# Sensores.net
KiCad netlist of a schematic drawn in Altium Designer
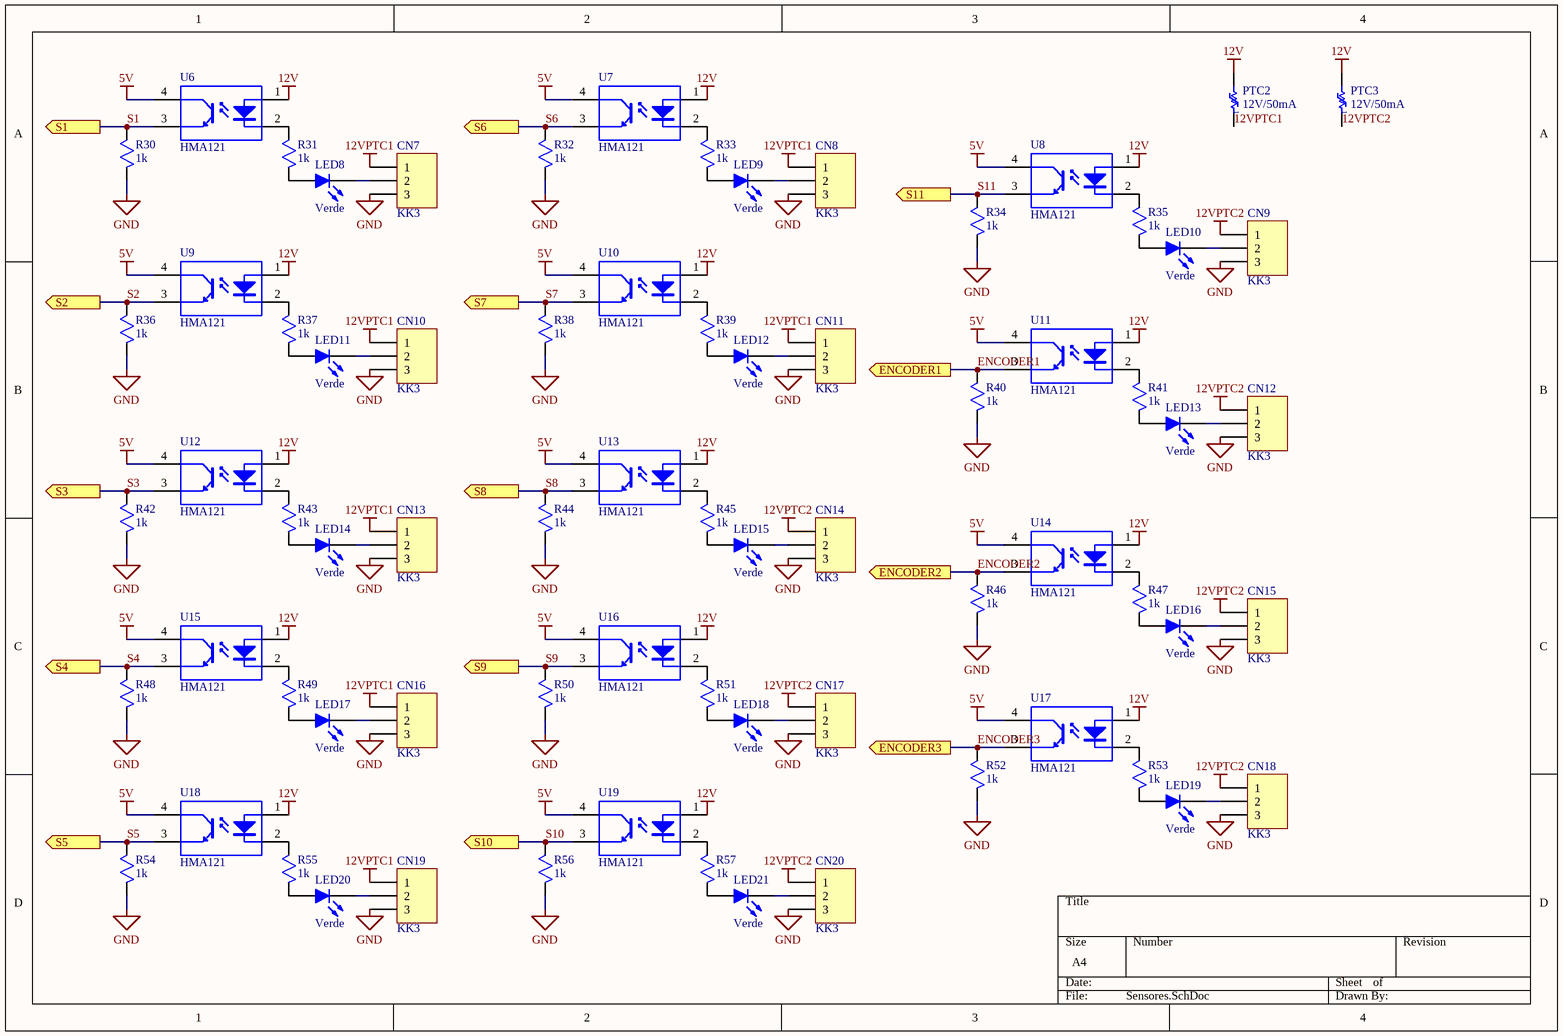
[diagram p0: Sensores.SchDoc]

(export (version "E")
  (design (tool "Eeschema 10.0.6"))
  (components
    (comp (ref "CN7")
      (value "KK3")
      (footprint "KK3 - 2.54mm")
      (description "Conector Linear tipo KK de 3 vias")
      (libsource (lib "conectores") (part "KK3"))
    )
    (comp (ref "CN8")
      (value "KK3")
      (footprint "KK3 - 2.54mm")
      (description "Conector Linear tipo KK de 3 vias")
      (libsource (lib "conectores") (part "KK3"))
    )
    (comp (ref "CN9")
      (value "KK3")
      (footprint "KK3 - 2.54mm")
      (description "Conector Linear tipo KK de 3 vias")
      (libsource (lib "conectores") (part "KK3"))
    )
    (comp (ref "CN10")
      (value "KK3")
      (footprint "KK3 - 2.54mm")
      (description "Conector Linear tipo KK de 3 vias")
      (libsource (lib "conectores") (part "KK3"))
    )
    (comp (ref "CN11")
      (value "KK3")
      (footprint "KK3 - 2.54mm")
      (description "Conector Linear tipo KK de 3 vias")
      (libsource (lib "conectores") (part "KK3"))
    )
    (comp (ref "CN12")
      (value "KK3")
      (footprint "KK3 - 2.54mm")
      (description "Conector Linear tipo KK de 3 vias")
      (libsource (lib "conectores") (part "KK3"))
    )
    (comp (ref "CN13")
      (value "KK3")
      (footprint "KK3 - 2.54mm")
      (description "Conector Linear tipo KK de 3 vias")
      (libsource (lib "conectores") (part "KK3"))
    )
    (comp (ref "CN14")
      (value "KK3")
      (footprint "KK3 - 2.54mm")
      (description "Conector Linear tipo KK de 3 vias")
      (libsource (lib "conectores") (part "KK3"))
    )
    (comp (ref "CN15")
      (value "KK3")
      (footprint "KK3 - 2.54mm")
      (description "Conector Linear tipo KK de 3 vias")
      (libsource (lib "conectores") (part "KK3"))
    )
    (comp (ref "CN16")
      (value "KK3")
      (footprint "KK3 - 2.54mm")
      (description "Conector Linear tipo KK de 3 vias")
      (libsource (lib "conectores") (part "KK3"))
    )
    (comp (ref "CN17")
      (value "KK3")
      (footprint "KK3 - 2.54mm")
      (description "Conector Linear tipo KK de 3 vias")
      (libsource (lib "conectores") (part "KK3"))
    )
    (comp (ref "CN18")
      (value "KK3")
      (footprint "KK3 - 2.54mm")
      (description "Conector Linear tipo KK de 3 vias")
      (libsource (lib "conectores") (part "KK3"))
    )
    (comp (ref "CN19")
      (value "KK3")
      (footprint "KK3 - 2.54mm")
      (description "Conector Linear tipo KK de 3 vias")
      (libsource (lib "conectores") (part "KK3"))
    )
    (comp (ref "CN20")
      (value "KK3")
      (footprint "KK3 - 2.54mm")
      (description "Conector Linear tipo KK de 3 vias")
      (libsource (lib "conectores") (part "KK3"))
    )
    (comp (ref "LED8")
      (value "Verde")
      (footprint "LED_SMD_0805")
      (description "Led")
      (fields (field (name "MANUFACTURER") "Generic Components") (field (name "PUBLISHER") "Altium Limited"))
      (libsource (lib "diodos_transistores") (part "Led"))
    )
    (comp (ref "LED9")
      (value "Verde")
      (footprint "LED_SMD_0805")
      (description "Led")
      (fields (field (name "MANUFACTURER") "Generic Components") (field (name "PUBLISHER") "Altium Limited"))
      (libsource (lib "diodos_transistores") (part "Led"))
    )
    (comp (ref "LED10")
      (value "Verde")
      (footprint "LED_SMD_0805")
      (description "Led")
      (fields (field (name "MANUFACTURER") "Generic Components") (field (name "PUBLISHER") "Altium Limited"))
      (libsource (lib "diodos_transistores") (part "Led"))
    )
    (comp (ref "LED11")
      (value "Verde")
      (footprint "LED_SMD_0805")
      (description "Led")
      (fields (field (name "MANUFACTURER") "Generic Components") (field (name "PUBLISHER") "Altium Limited"))
      (libsource (lib "diodos_transistores") (part "Led"))
    )
    (comp (ref "LED12")
      (value "Verde")
      (footprint "LED_SMD_0805")
      (description "Led")
      (fields (field (name "MANUFACTURER") "Generic Components") (field (name "PUBLISHER") "Altium Limited"))
      (libsource (lib "diodos_transistores") (part "Led"))
    )
    (comp (ref "LED13")
      (value "Verde")
      (footprint "LED_SMD_0805")
      (description "Led")
      (fields (field (name "MANUFACTURER") "Generic Components") (field (name "PUBLISHER") "Altium Limited"))
      (libsource (lib "diodos_transistores") (part "Led"))
    )
    (comp (ref "LED14")
      (value "Verde")
      (footprint "LED_SMD_0805")
      (description "Led")
      (fields (field (name "MANUFACTURER") "Generic Components") (field (name "PUBLISHER") "Altium Limited"))
      (libsource (lib "diodos_transistores") (part "Led"))
    )
    (comp (ref "LED15")
      (value "Verde")
      (footprint "LED_SMD_0805")
      (description "Led")
      (fields (field (name "MANUFACTURER") "Generic Components") (field (name "PUBLISHER") "Altium Limited"))
      (libsource (lib "diodos_transistores") (part "Led"))
    )
    (comp (ref "LED16")
      (value "Verde")
      (footprint "LED_SMD_0805")
      (description "Led")
      (fields (field (name "MANUFACTURER") "Generic Components") (field (name "PUBLISHER") "Altium Limited"))
      (libsource (lib "diodos_transistores") (part "Led"))
    )
    (comp (ref "LED17")
      (value "Verde")
      (footprint "LED_SMD_0805")
      (description "Led")
      (fields (field (name "MANUFACTURER") "Generic Components") (field (name "PUBLISHER") "Altium Limited"))
      (libsource (lib "diodos_transistores") (part "Led"))
    )
    (comp (ref "LED18")
      (value "Verde")
      (footprint "LED_SMD_0805")
      (description "Led")
      (fields (field (name "MANUFACTURER") "Generic Components") (field (name "PUBLISHER") "Altium Limited"))
      (libsource (lib "diodos_transistores") (part "Led"))
    )
    (comp (ref "LED19")
      (value "Verde")
      (footprint "LED_SMD_0805")
      (description "Led")
      (fields (field (name "MANUFACTURER") "Generic Components") (field (name "PUBLISHER") "Altium Limited"))
      (libsource (lib "diodos_transistores") (part "Led"))
    )
    (comp (ref "LED20")
      (value "Verde")
      (footprint "LED_SMD_0805")
      (description "Led")
      (fields (field (name "MANUFACTURER") "Generic Components") (field (name "PUBLISHER") "Altium Limited"))
      (libsource (lib "diodos_transistores") (part "Led"))
    )
    (comp (ref "LED21")
      (value "Verde")
      (footprint "LED_SMD_0805")
      (description "Led")
      (fields (field (name "MANUFACTURER") "Generic Components") (field (name "PUBLISHER") "Altium Limited"))
      (libsource (lib "diodos_transistores") (part "Led"))
    )
    (comp (ref "PTC2")
      (value "12V/50mA")
      (footprint "PTC-200")
      (description "Termistor")
      (libsource (lib "comps_passivos") (part "PTC"))
    )
    (comp (ref "PTC3")
      (value "12V/50mA")
      (footprint "PTC-200")
      (description "Termistor")
      (libsource (lib "comps_passivos") (part "PTC"))
    )
    (comp (ref "R30")
      (value "1k")
      (footprint "SMD0805")
      (description "Resistor")
      (libsource (lib "passivos") (part "Resistor"))
    )
    (comp (ref "R31")
      (value "1k")
      (footprint "SMD0805")
      (description "Resistor")
      (libsource (lib "passivos") (part "Resistor"))
    )
    (comp (ref "R32")
      (value "1k")
      (footprint "SMD0805")
      (description "Resistor")
      (libsource (lib "passivos") (part "Resistor"))
    )
    (comp (ref "R33")
      (value "1k")
      (footprint "SMD0805")
      (description "Resistor")
      (libsource (lib "passivos") (part "Resistor"))
    )
    (comp (ref "R34")
      (value "1k")
      (footprint "SMD0805")
      (description "Resistor")
      (libsource (lib "passivos") (part "Resistor"))
    )
    (comp (ref "R35")
      (value "1k")
      (footprint "SMD0805")
      (description "Resistor")
      (libsource (lib "passivos") (part "Resistor"))
    )
    (comp (ref "R36")
      (value "1k")
      (footprint "SMD0805")
      (description "Resistor")
      (libsource (lib "passivos") (part "Resistor"))
    )
    (comp (ref "R37")
      (value "1k")
      (footprint "SMD0805")
      (description "Resistor")
      (libsource (lib "passivos") (part "Resistor"))
    )
    (comp (ref "R38")
      (value "1k")
      (footprint "SMD0805")
      (description "Resistor")
      (libsource (lib "passivos") (part "Resistor"))
    )
    (comp (ref "R39")
      (value "1k")
      (footprint "SMD0805")
      (description "Resistor")
      (libsource (lib "passivos") (part "Resistor"))
    )
    (comp (ref "R40")
      (value "1k")
      (footprint "SMD0805")
      (description "Resistor")
      (libsource (lib "passivos") (part "Resistor"))
    )
    (comp (ref "R41")
      (value "1k")
      (footprint "SMD0805")
      (description "Resistor")
      (libsource (lib "passivos") (part "Resistor"))
    )
    (comp (ref "R42")
      (value "1k")
      (footprint "SMD0805")
      (description "Resistor")
      (libsource (lib "passivos") (part "Resistor"))
    )
    (comp (ref "R43")
      (value "1k")
      (footprint "SMD0805")
      (description "Resistor")
      (libsource (lib "passivos") (part "Resistor"))
    )
    (comp (ref "R44")
      (value "1k")
      (footprint "SMD0805")
      (description "Resistor")
      (libsource (lib "passivos") (part "Resistor"))
    )
    (comp (ref "R45")
      (value "1k")
      (footprint "SMD0805")
      (description "Resistor")
      (libsource (lib "passivos") (part "Resistor"))
    )
    (comp (ref "R46")
      (value "1k")
      (footprint "SMD0805")
      (description "Resistor")
      (libsource (lib "passivos") (part "Resistor"))
    )
    (comp (ref "R47")
      (value "1k")
      (footprint "SMD0805")
      (description "Resistor")
      (libsource (lib "passivos") (part "Resistor"))
    )
    (comp (ref "R48")
      (value "1k")
      (footprint "SMD0805")
      (description "Resistor")
      (libsource (lib "passivos") (part "Resistor"))
    )
    (comp (ref "R49")
      (value "1k")
      (footprint "SMD0805")
      (description "Resistor")
      (libsource (lib "passivos") (part "Resistor"))
    )
    (comp (ref "R50")
      (value "1k")
      (footprint "SMD0805")
      (description "Resistor")
      (libsource (lib "passivos") (part "Resistor"))
    )
    (comp (ref "R51")
      (value "1k")
      (footprint "SMD0805")
      (description "Resistor")
      (libsource (lib "passivos") (part "Resistor"))
    )
    (comp (ref "R52")
      (value "1k")
      (footprint "SMD0805")
      (description "Resistor")
      (libsource (lib "passivos") (part "Resistor"))
    )
    (comp (ref "R53")
      (value "1k")
      (footprint "SMD0805")
      (description "Resistor")
      (libsource (lib "passivos") (part "Resistor"))
    )
    (comp (ref "R54")
      (value "1k")
      (footprint "SMD0805")
      (description "Resistor")
      (libsource (lib "passivos") (part "Resistor"))
    )
    (comp (ref "R55")
      (value "1k")
      (footprint "SMD0805")
      (description "Resistor")
      (libsource (lib "passivos") (part "Resistor"))
    )
    (comp (ref "R56")
      (value "1k")
      (footprint "SMD0805")
      (description "Resistor")
      (libsource (lib "passivos") (part "Resistor"))
    )
    (comp (ref "R57")
      (value "1k")
      (footprint "SMD0805")
      (description "Resistor")
      (libsource (lib "passivos") (part "Resistor"))
    )
    (comp (ref "U6")
      (value "HMA121")
      (footprint "SO4")
      (description "Phototransistor Optocoupler SMD full Pptch mini-flat type")
      (fields (field (name "MANUFACTURER") "Generic Components") (field (name "PUBLISHER") "Altium Limited"))
      (libsource (lib "diodos_transistores") (part "HMA"))
    )
    (comp (ref "U7")
      (value "HMA121")
      (footprint "SO4")
      (description "Phototransistor Optocoupler SMD full Pptch mini-flat type")
      (fields (field (name "MANUFACTURER") "Generic Components") (field (name "PUBLISHER") "Altium Limited"))
      (libsource (lib "diodos_transistores") (part "HMA"))
    )
    (comp (ref "U8")
      (value "HMA121")
      (footprint "SO4")
      (description "Phototransistor Optocoupler SMD full Pptch mini-flat type")
      (fields (field (name "MANUFACTURER") "Generic Components") (field (name "PUBLISHER") "Altium Limited"))
      (libsource (lib "diodos_transistores") (part "HMA"))
    )
    (comp (ref "U9")
      (value "HMA121")
      (footprint "SO4")
      (description "Phototransistor Optocoupler SMD full Pptch mini-flat type")
      (fields (field (name "MANUFACTURER") "Generic Components") (field (name "PUBLISHER") "Altium Limited"))
      (libsource (lib "diodos_transistores") (part "HMA"))
    )
    (comp (ref "U10")
      (value "HMA121")
      (footprint "SO4")
      (description "Phototransistor Optocoupler SMD full Pptch mini-flat type")
      (fields (field (name "MANUFACTURER") "Generic Components") (field (name "PUBLISHER") "Altium Limited"))
      (libsource (lib "diodos_transistores") (part "HMA"))
    )
    (comp (ref "U11")
      (value "HMA121")
      (footprint "SO4")
      (description "Phototransistor Optocoupler SMD full Pptch mini-flat type")
      (fields (field (name "MANUFACTURER") "Generic Components") (field (name "PUBLISHER") "Altium Limited"))
      (libsource (lib "diodos_transistores") (part "HMA"))
    )
    (comp (ref "U12")
      (value "HMA121")
      (footprint "SO4")
      (description "Phototransistor Optocoupler SMD full Pptch mini-flat type")
      (fields (field (name "MANUFACTURER") "Generic Components") (field (name "PUBLISHER") "Altium Limited"))
      (libsource (lib "diodos_transistores") (part "HMA"))
    )
    (comp (ref "U13")
      (value "HMA121")
      (footprint "SO4")
      (description "Phototransistor Optocoupler SMD full Pptch mini-flat type")
      (fields (field (name "MANUFACTURER") "Generic Components") (field (name "PUBLISHER") "Altium Limited"))
      (libsource (lib "diodos_transistores") (part "HMA"))
    )
    (comp (ref "U14")
      (value "HMA121")
      (footprint "SO4")
      (description "Phototransistor Optocoupler SMD full Pptch mini-flat type")
      (fields (field (name "MANUFACTURER") "Generic Components") (field (name "PUBLISHER") "Altium Limited"))
      (libsource (lib "diodos_transistores") (part "HMA"))
    )
    (comp (ref "U15")
      (value "HMA121")
      (footprint "SO4")
      (description "Phototransistor Optocoupler SMD full Pptch mini-flat type")
      (fields (field (name "MANUFACTURER") "Generic Components") (field (name "PUBLISHER") "Altium Limited"))
      (libsource (lib "diodos_transistores") (part "HMA"))
    )
    (comp (ref "U16")
      (value "HMA121")
      (footprint "SO4")
      (description "Phototransistor Optocoupler SMD full Pptch mini-flat type")
      (fields (field (name "MANUFACTURER") "Generic Components") (field (name "PUBLISHER") "Altium Limited"))
      (libsource (lib "diodos_transistores") (part "HMA"))
    )
    (comp (ref "U17")
      (value "HMA121")
      (footprint "SO4")
      (description "Phototransistor Optocoupler SMD full Pptch mini-flat type")
      (fields (field (name "MANUFACTURER") "Generic Components") (field (name "PUBLISHER") "Altium Limited"))
      (libsource (lib "diodos_transistores") (part "HMA"))
    )
    (comp (ref "U18")
      (value "HMA121")
      (footprint "SO4")
      (description "Phototransistor Optocoupler SMD full Pptch mini-flat type")
      (fields (field (name "MANUFACTURER") "Generic Components") (field (name "PUBLISHER") "Altium Limited"))
      (libsource (lib "diodos_transistores") (part "HMA"))
    )
    (comp (ref "U19")
      (value "HMA121")
      (footprint "SO4")
      (description "Phototransistor Optocoupler SMD full Pptch mini-flat type")
      (fields (field (name "MANUFACTURER") "Generic Components") (field (name "PUBLISHER") "Altium Limited"))
      (libsource (lib "diodos_transistores") (part "HMA"))
    )
  )
  (nets
    (net (code "1") (name "/ENCODER1") (class "Default")
      (node (ref "R40") (pin "1") (pinfunction "1_1") (pintype "passive"))
      (node (ref "U11") (pin "3") (pinfunction "E_3") (pintype "passive"))
    )
    (net (code "2") (name "/ENCODER2") (class "Default")
      (node (ref "R46") (pin "1") (pinfunction "1_1") (pintype "passive"))
      (node (ref "U14") (pin "3") (pinfunction "E_3") (pintype "passive"))
    )
    (net (code "3") (name "/ENCODER3") (class "Default")
      (node (ref "R52") (pin "1") (pinfunction "1_1") (pintype "passive"))
      (node (ref "U17") (pin "3") (pinfunction "E_3") (pintype "passive"))
    )
    (net (code "4") (name "/S1") (class "Default")
      (node (ref "R30") (pin "1") (pinfunction "1_1") (pintype "passive"))
      (node (ref "U6") (pin "3") (pinfunction "E_3") (pintype "passive"))
    )
    (net (code "5") (name "/S2") (class "Default")
      (node (ref "R36") (pin "1") (pinfunction "1_1") (pintype "passive"))
      (node (ref "U9") (pin "3") (pinfunction "E_3") (pintype "passive"))
    )
    (net (code "6") (name "/S3") (class "Default")
      (node (ref "R42") (pin "1") (pinfunction "1_1") (pintype "passive"))
      (node (ref "U12") (pin "3") (pinfunction "E_3") (pintype "passive"))
    )
    (net (code "7") (name "/S4") (class "Default")
      (node (ref "R48") (pin "1") (pinfunction "1_1") (pintype "passive"))
      (node (ref "U15") (pin "3") (pinfunction "E_3") (pintype "passive"))
    )
    (net (code "8") (name "/S5") (class "Default")
      (node (ref "R54") (pin "1") (pinfunction "1_1") (pintype "passive"))
      (node (ref "U18") (pin "3") (pinfunction "E_3") (pintype "passive"))
    )
    (net (code "9") (name "/S6") (class "Default")
      (node (ref "R32") (pin "1") (pinfunction "1_1") (pintype "passive"))
      (node (ref "U7") (pin "3") (pinfunction "E_3") (pintype "passive"))
    )
    (net (code "10") (name "/S7") (class "Default")
      (node (ref "R38") (pin "1") (pinfunction "1_1") (pintype "passive"))
      (node (ref "U10") (pin "3") (pinfunction "E_3") (pintype "passive"))
    )
    (net (code "11") (name "/S8") (class "Default")
      (node (ref "R44") (pin "1") (pinfunction "1_1") (pintype "passive"))
      (node (ref "U13") (pin "3") (pinfunction "E_3") (pintype "passive"))
    )
    (net (code "12") (name "/S9") (class "Default")
      (node (ref "R50") (pin "1") (pinfunction "1_1") (pintype "passive"))
      (node (ref "U16") (pin "3") (pinfunction "E_3") (pintype "passive"))
    )
    (net (code "13") (name "/S10") (class "Default")
      (node (ref "R56") (pin "1") (pinfunction "1_1") (pintype "passive"))
      (node (ref "U19") (pin "3") (pinfunction "E_3") (pintype "passive"))
    )
    (net (code "14") (name "/S11") (class "Default")
      (node (ref "R34") (pin "1") (pinfunction "1_1") (pintype "passive"))
      (node (ref "U8") (pin "3") (pinfunction "E_3") (pintype "passive"))
    )
    (net (code "15") (name "5V") (class "Default")
      (node (ref "U10") (pin "4") (pinfunction "C_4") (pintype "passive"))
      (node (ref "U11") (pin "4") (pinfunction "C_4") (pintype "passive"))
      (node (ref "U12") (pin "4") (pinfunction "C_4") (pintype "passive"))
      (node (ref "U13") (pin "4") (pinfunction "C_4") (pintype "passive"))
      (node (ref "U14") (pin "4") (pinfunction "C_4") (pintype "passive"))
      (node (ref "U15") (pin "4") (pinfunction "C_4") (pintype "passive"))
      (node (ref "U16") (pin "4") (pinfunction "C_4") (pintype "passive"))
      (node (ref "U17") (pin "4") (pinfunction "C_4") (pintype "passive"))
      (node (ref "U18") (pin "4") (pinfunction "C_4") (pintype "passive"))
      (node (ref "U19") (pin "4") (pinfunction "C_4") (pintype "passive"))
      (node (ref "U6") (pin "4") (pinfunction "C_4") (pintype "passive"))
      (node (ref "U7") (pin "4") (pinfunction "C_4") (pintype "passive"))
      (node (ref "U8") (pin "4") (pinfunction "C_4") (pintype "passive"))
      (node (ref "U9") (pin "4") (pinfunction "C_4") (pintype "passive"))
    )
    (net (code "16") (name "12V") (class "Default")
      (node (ref "PTC2") (pin "2") (pinfunction "2_2") (pintype "passive"))
      (node (ref "PTC3") (pin "2") (pinfunction "2_2") (pintype "passive"))
      (node (ref "U10") (pin "1") (pinfunction "A_1") (pintype "passive"))
      (node (ref "U11") (pin "1") (pinfunction "A_1") (pintype "passive"))
      (node (ref "U12") (pin "1") (pinfunction "A_1") (pintype "passive"))
      (node (ref "U13") (pin "1") (pinfunction "A_1") (pintype "passive"))
      (node (ref "U14") (pin "1") (pinfunction "A_1") (pintype "passive"))
      (node (ref "U15") (pin "1") (pinfunction "A_1") (pintype "passive"))
      (node (ref "U16") (pin "1") (pinfunction "A_1") (pintype "passive"))
      (node (ref "U17") (pin "1") (pinfunction "A_1") (pintype "passive"))
      (node (ref "U18") (pin "1") (pinfunction "A_1") (pintype "passive"))
      (node (ref "U19") (pin "1") (pinfunction "A_1") (pintype "passive"))
      (node (ref "U6") (pin "1") (pinfunction "A_1") (pintype "passive"))
      (node (ref "U7") (pin "1") (pinfunction "A_1") (pintype "passive"))
      (node (ref "U8") (pin "1") (pinfunction "A_1") (pintype "passive"))
      (node (ref "U9") (pin "1") (pinfunction "A_1") (pintype "passive"))
    )
    (net (code "17") (name "12VPTC1") (class "Default")
      (node (ref "CN10") (pin "1") (pinfunction "1_1") (pintype "passive"))
      (node (ref "CN11") (pin "1") (pinfunction "1_1") (pintype "passive"))
      (node (ref "CN13") (pin "1") (pinfunction "1_1") (pintype "passive"))
      (node (ref "CN16") (pin "1") (pinfunction "1_1") (pintype "passive"))
      (node (ref "CN19") (pin "1") (pinfunction "1_1") (pintype "passive"))
      (node (ref "CN7") (pin "1") (pinfunction "1_1") (pintype "passive"))
      (node (ref "CN8") (pin "1") (pinfunction "1_1") (pintype "passive"))
      (node (ref "PTC2") (pin "1") (pinfunction "1_1") (pintype "passive"))
    )
    (net (code "18") (name "12VPTC2") (class "Default")
      (node (ref "CN12") (pin "1") (pinfunction "1_1") (pintype "passive"))
      (node (ref "CN14") (pin "1") (pinfunction "1_1") (pintype "passive"))
      (node (ref "CN15") (pin "1") (pinfunction "1_1") (pintype "passive"))
      (node (ref "CN17") (pin "1") (pinfunction "1_1") (pintype "passive"))
      (node (ref "CN18") (pin "1") (pinfunction "1_1") (pintype "passive"))
      (node (ref "CN20") (pin "1") (pinfunction "1_1") (pintype "passive"))
      (node (ref "CN9") (pin "1") (pinfunction "1_1") (pintype "passive"))
      (node (ref "PTC3") (pin "1") (pinfunction "1_1") (pintype "passive"))
    )
    (net (code "19") (name "GND") (class "Default")
      (node (ref "CN10") (pin "3") (pinfunction "3_3") (pintype "passive"))
      (node (ref "CN11") (pin "3") (pinfunction "3_3") (pintype "passive"))
      (node (ref "CN12") (pin "3") (pinfunction "3_3") (pintype "passive"))
      (node (ref "CN13") (pin "3") (pinfunction "3_3") (pintype "passive"))
      (node (ref "CN14") (pin "3") (pinfunction "3_3") (pintype "passive"))
      (node (ref "CN15") (pin "3") (pinfunction "3_3") (pintype "passive"))
      (node (ref "CN16") (pin "3") (pinfunction "3_3") (pintype "passive"))
      (node (ref "CN17") (pin "3") (pinfunction "3_3") (pintype "passive"))
      (node (ref "CN18") (pin "3") (pinfunction "3_3") (pintype "passive"))
      (node (ref "CN19") (pin "3") (pinfunction "3_3") (pintype "passive"))
      (node (ref "CN20") (pin "3") (pinfunction "3_3") (pintype "passive"))
      (node (ref "CN7") (pin "3") (pinfunction "3_3") (pintype "passive"))
      (node (ref "CN8") (pin "3") (pinfunction "3_3") (pintype "passive"))
      (node (ref "CN9") (pin "3") (pinfunction "3_3") (pintype "passive"))
      (node (ref "R30") (pin "2") (pinfunction "2_2") (pintype "passive"))
      (node (ref "R32") (pin "2") (pinfunction "2_2") (pintype "passive"))
      (node (ref "R34") (pin "2") (pinfunction "2_2") (pintype "passive"))
      (node (ref "R36") (pin "2") (pinfunction "2_2") (pintype "passive"))
      (node (ref "R38") (pin "2") (pinfunction "2_2") (pintype "passive"))
      (node (ref "R40") (pin "2") (pinfunction "2_2") (pintype "passive"))
      (node (ref "R42") (pin "2") (pinfunction "2_2") (pintype "passive"))
      (node (ref "R44") (pin "2") (pinfunction "2_2") (pintype "passive"))
      (node (ref "R46") (pin "2") (pinfunction "2_2") (pintype "passive"))
      (node (ref "R48") (pin "2") (pinfunction "2_2") (pintype "passive"))
      (node (ref "R50") (pin "2") (pinfunction "2_2") (pintype "passive"))
      (node (ref "R52") (pin "2") (pinfunction "2_2") (pintype "passive"))
      (node (ref "R54") (pin "2") (pinfunction "2_2") (pintype "passive"))
      (node (ref "R56") (pin "2") (pinfunction "2_2") (pintype "passive"))
    )
    (net (code "20") (name "Net-(LED8-A)") (class "Default")
      (node (ref "LED8") (pin "1") (pinfunction "A_1") (pintype "passive"))
      (node (ref "R31") (pin "1") (pinfunction "1_1") (pintype "passive"))
    )
    (net (code "21") (name "Net-(LED8-K)") (class "Default")
      (node (ref "CN7") (pin "2") (pinfunction "2_2") (pintype "passive"))
      (node (ref "LED8") (pin "2") (pinfunction "K_2") (pintype "passive"))
    )
    (net (code "22") (name "Net-(LED9-A)") (class "Default")
      (node (ref "LED9") (pin "1") (pinfunction "A_1") (pintype "passive"))
      (node (ref "R33") (pin "1") (pinfunction "1_1") (pintype "passive"))
    )
    (net (code "23") (name "Net-(LED9-K)") (class "Default")
      (node (ref "CN8") (pin "2") (pinfunction "2_2") (pintype "passive"))
      (node (ref "LED9") (pin "2") (pinfunction "K_2") (pintype "passive"))
    )
    (net (code "24") (name "Net-(LED10-A)") (class "Default")
      (node (ref "LED10") (pin "1") (pinfunction "A_1") (pintype "passive"))
      (node (ref "R35") (pin "1") (pinfunction "1_1") (pintype "passive"))
    )
    (net (code "25") (name "Net-(LED10-K)") (class "Default")
      (node (ref "CN9") (pin "2") (pinfunction "2_2") (pintype "passive"))
      (node (ref "LED10") (pin "2") (pinfunction "K_2") (pintype "passive"))
    )
    (net (code "26") (name "Net-(LED11-A)") (class "Default")
      (node (ref "LED11") (pin "1") (pinfunction "A_1") (pintype "passive"))
      (node (ref "R37") (pin "1") (pinfunction "1_1") (pintype "passive"))
    )
    (net (code "27") (name "Net-(LED11-K)") (class "Default")
      (node (ref "CN10") (pin "2") (pinfunction "2_2") (pintype "passive"))
      (node (ref "LED11") (pin "2") (pinfunction "K_2") (pintype "passive"))
    )
    (net (code "28") (name "Net-(LED12-A)") (class "Default")
      (node (ref "LED12") (pin "1") (pinfunction "A_1") (pintype "passive"))
      (node (ref "R39") (pin "1") (pinfunction "1_1") (pintype "passive"))
    )
    (net (code "29") (name "Net-(LED12-K)") (class "Default")
      (node (ref "CN11") (pin "2") (pinfunction "2_2") (pintype "passive"))
      (node (ref "LED12") (pin "2") (pinfunction "K_2") (pintype "passive"))
    )
    (net (code "30") (name "Net-(LED13-A)") (class "Default")
      (node (ref "LED13") (pin "1") (pinfunction "A_1") (pintype "passive"))
      (node (ref "R41") (pin "1") (pinfunction "1_1") (pintype "passive"))
    )
    (net (code "31") (name "Net-(LED13-K)") (class "Default")
      (node (ref "CN12") (pin "2") (pinfunction "2_2") (pintype "passive"))
      (node (ref "LED13") (pin "2") (pinfunction "K_2") (pintype "passive"))
    )
    (net (code "32") (name "Net-(LED14-A)") (class "Default")
      (node (ref "LED14") (pin "1") (pinfunction "A_1") (pintype "passive"))
      (node (ref "R43") (pin "1") (pinfunction "1_1") (pintype "passive"))
    )
    (net (code "33") (name "Net-(LED14-K)") (class "Default")
      (node (ref "CN13") (pin "2") (pinfunction "2_2") (pintype "passive"))
      (node (ref "LED14") (pin "2") (pinfunction "K_2") (pintype "passive"))
    )
    (net (code "34") (name "Net-(LED15-A)") (class "Default")
      (node (ref "LED15") (pin "1") (pinfunction "A_1") (pintype "passive"))
      (node (ref "R45") (pin "1") (pinfunction "1_1") (pintype "passive"))
    )
    (net (code "35") (name "Net-(LED15-K)") (class "Default")
      (node (ref "CN14") (pin "2") (pinfunction "2_2") (pintype "passive"))
      (node (ref "LED15") (pin "2") (pinfunction "K_2") (pintype "passive"))
    )
    (net (code "36") (name "Net-(LED16-A)") (class "Default")
      (node (ref "LED16") (pin "1") (pinfunction "A_1") (pintype "passive"))
      (node (ref "R47") (pin "1") (pinfunction "1_1") (pintype "passive"))
    )
    (net (code "37") (name "Net-(LED16-K)") (class "Default")
      (node (ref "CN15") (pin "2") (pinfunction "2_2") (pintype "passive"))
      (node (ref "LED16") (pin "2") (pinfunction "K_2") (pintype "passive"))
    )
    (net (code "38") (name "Net-(LED17-A)") (class "Default")
      (node (ref "LED17") (pin "1") (pinfunction "A_1") (pintype "passive"))
      (node (ref "R49") (pin "1") (pinfunction "1_1") (pintype "passive"))
    )
    (net (code "39") (name "Net-(LED17-K)") (class "Default")
      (node (ref "CN16") (pin "2") (pinfunction "2_2") (pintype "passive"))
      (node (ref "LED17") (pin "2") (pinfunction "K_2") (pintype "passive"))
    )
    (net (code "40") (name "Net-(LED18-A)") (class "Default")
      (node (ref "LED18") (pin "1") (pinfunction "A_1") (pintype "passive"))
      (node (ref "R51") (pin "1") (pinfunction "1_1") (pintype "passive"))
    )
    (net (code "41") (name "Net-(LED18-K)") (class "Default")
      (node (ref "CN17") (pin "2") (pinfunction "2_2") (pintype "passive"))
      (node (ref "LED18") (pin "2") (pinfunction "K_2") (pintype "passive"))
    )
    (net (code "42") (name "Net-(LED19-A)") (class "Default")
      (node (ref "LED19") (pin "1") (pinfunction "A_1") (pintype "passive"))
      (node (ref "R53") (pin "1") (pinfunction "1_1") (pintype "passive"))
    )
    (net (code "43") (name "Net-(LED19-K)") (class "Default")
      (node (ref "CN18") (pin "2") (pinfunction "2_2") (pintype "passive"))
      (node (ref "LED19") (pin "2") (pinfunction "K_2") (pintype "passive"))
    )
    (net (code "44") (name "Net-(LED20-A)") (class "Default")
      (node (ref "LED20") (pin "1") (pinfunction "A_1") (pintype "passive"))
      (node (ref "R55") (pin "1") (pinfunction "1_1") (pintype "passive"))
    )
    (net (code "45") (name "Net-(LED20-K)") (class "Default")
      (node (ref "CN19") (pin "2") (pinfunction "2_2") (pintype "passive"))
      (node (ref "LED20") (pin "2") (pinfunction "K_2") (pintype "passive"))
    )
    (net (code "46") (name "Net-(LED21-A)") (class "Default")
      (node (ref "LED21") (pin "1") (pinfunction "A_1") (pintype "passive"))
      (node (ref "R57") (pin "1") (pinfunction "1_1") (pintype "passive"))
    )
    (net (code "47") (name "Net-(LED21-K)") (class "Default")
      (node (ref "CN20") (pin "2") (pinfunction "2_2") (pintype "passive"))
      (node (ref "LED21") (pin "2") (pinfunction "K_2") (pintype "passive"))
    )
    (net (code "48") (name "Net-(U6-K)") (class "Default")
      (node (ref "R31") (pin "2") (pinfunction "2_2") (pintype "passive"))
      (node (ref "U6") (pin "2") (pinfunction "K_2") (pintype "passive"))
    )
    (net (code "49") (name "Net-(U7-K)") (class "Default")
      (node (ref "R33") (pin "2") (pinfunction "2_2") (pintype "passive"))
      (node (ref "U7") (pin "2") (pinfunction "K_2") (pintype "passive"))
    )
    (net (code "50") (name "Net-(U8-K)") (class "Default")
      (node (ref "R35") (pin "2") (pinfunction "2_2") (pintype "passive"))
      (node (ref "U8") (pin "2") (pinfunction "K_2") (pintype "passive"))
    )
    (net (code "51") (name "Net-(U9-K)") (class "Default")
      (node (ref "R37") (pin "2") (pinfunction "2_2") (pintype "passive"))
      (node (ref "U9") (pin "2") (pinfunction "K_2") (pintype "passive"))
    )
    (net (code "52") (name "Net-(U10-K)") (class "Default")
      (node (ref "R39") (pin "2") (pinfunction "2_2") (pintype "passive"))
      (node (ref "U10") (pin "2") (pinfunction "K_2") (pintype "passive"))
    )
    (net (code "53") (name "Net-(U11-K)") (class "Default")
      (node (ref "R41") (pin "2") (pinfunction "2_2") (pintype "passive"))
      (node (ref "U11") (pin "2") (pinfunction "K_2") (pintype "passive"))
    )
    (net (code "54") (name "Net-(U12-K)") (class "Default")
      (node (ref "R43") (pin "2") (pinfunction "2_2") (pintype "passive"))
      (node (ref "U12") (pin "2") (pinfunction "K_2") (pintype "passive"))
    )
    (net (code "55") (name "Net-(U13-K)") (class "Default")
      (node (ref "R45") (pin "2") (pinfunction "2_2") (pintype "passive"))
      (node (ref "U13") (pin "2") (pinfunction "K_2") (pintype "passive"))
    )
    (net (code "56") (name "Net-(U14-K)") (class "Default")
      (node (ref "R47") (pin "2") (pinfunction "2_2") (pintype "passive"))
      (node (ref "U14") (pin "2") (pinfunction "K_2") (pintype "passive"))
    )
    (net (code "57") (name "Net-(U15-K)") (class "Default")
      (node (ref "R49") (pin "2") (pinfunction "2_2") (pintype "passive"))
      (node (ref "U15") (pin "2") (pinfunction "K_2") (pintype "passive"))
    )
    (net (code "58") (name "Net-(U16-K)") (class "Default")
      (node (ref "R51") (pin "2") (pinfunction "2_2") (pintype "passive"))
      (node (ref "U16") (pin "2") (pinfunction "K_2") (pintype "passive"))
    )
    (net (code "59") (name "Net-(U17-K)") (class "Default")
      (node (ref "R53") (pin "2") (pinfunction "2_2") (pintype "passive"))
      (node (ref "U17") (pin "2") (pinfunction "K_2") (pintype "passive"))
    )
    (net (code "60") (name "Net-(U18-K)") (class "Default")
      (node (ref "R55") (pin "2") (pinfunction "2_2") (pintype "passive"))
      (node (ref "U18") (pin "2") (pinfunction "K_2") (pintype "passive"))
    )
    (net (code "61") (name "Net-(U19-K)") (class "Default")
      (node (ref "R57") (pin "2") (pinfunction "2_2") (pintype "passive"))
      (node (ref "U19") (pin "2") (pinfunction "K_2") (pintype "passive"))
    )
  )
)
